# ink_driver.net
KiCad netlist of a schematic drawn in EAGLE
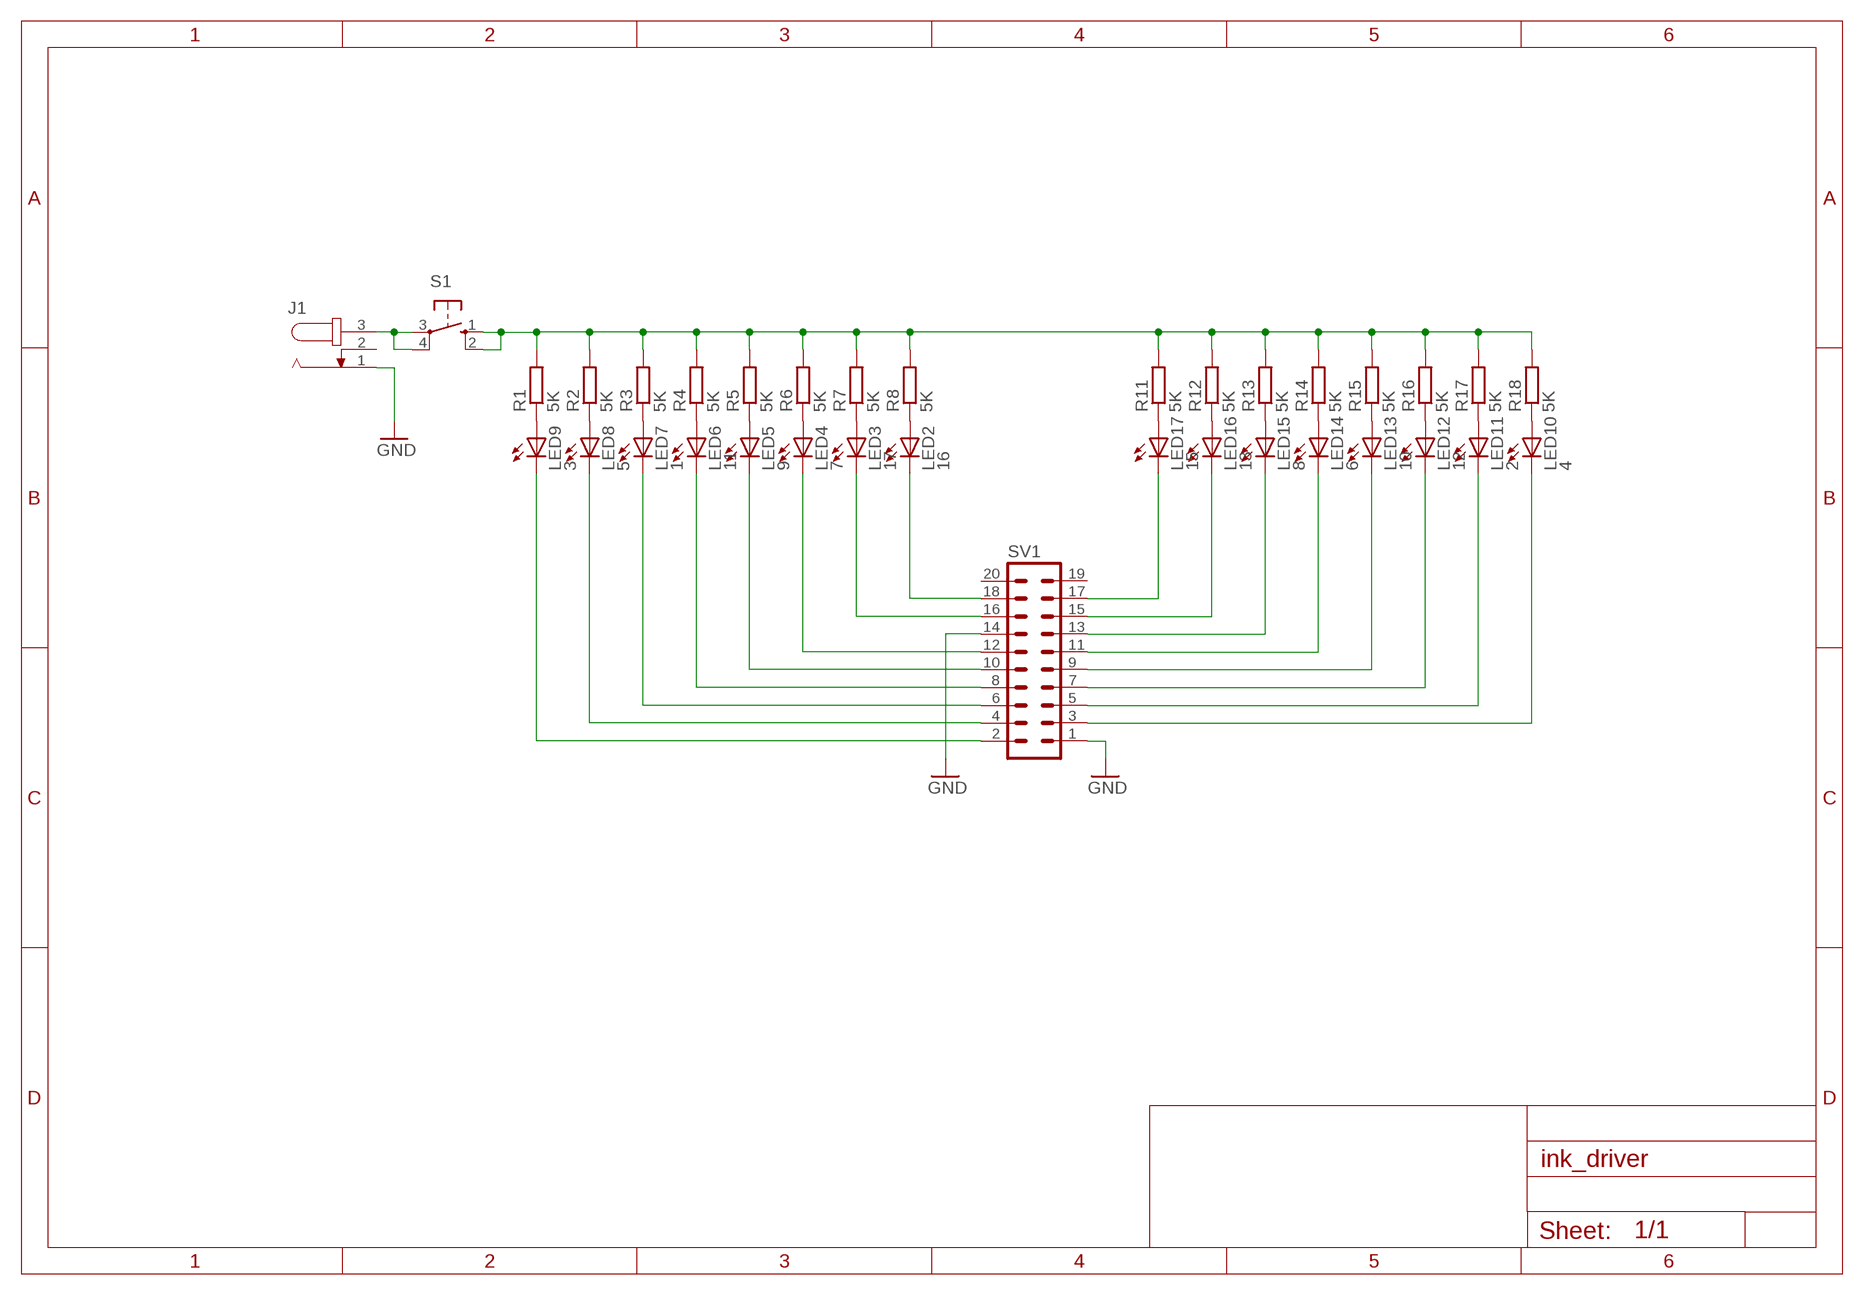
[diagram p0: schematic, sheet 1]

(export (version "E")
  (design (tool "Eeschema 10.0.6"))
  (components
    (comp (ref "J1")
      (value "JACK-PLUG1")
      (footprint "eagle-import:SPC4078")
      (libsource (lib "eagle-import") (part "JACK-PLUG1"))
    )
    (comp (ref "LED2")
      (value "16")
      (footprint "eagle-import:LED3MM")
      (libsource (lib "eagle-import") (part "LED3MM"))
    )
    (comp (ref "LED3")
      (value "17")
      (footprint "eagle-import:LED3MM")
      (libsource (lib "eagle-import") (part "LED3MM"))
    )
    (comp (ref "LED4")
      (value "7")
      (footprint "eagle-import:LED3MM")
      (libsource (lib "eagle-import") (part "LED3MM"))
    )
    (comp (ref "LED5")
      (value "9")
      (footprint "eagle-import:LED3MM")
      (libsource (lib "eagle-import") (part "LED3MM"))
    )
    (comp (ref "LED6")
      (value "11")
      (footprint "eagle-import:LED3MM")
      (libsource (lib "eagle-import") (part "LED3MM"))
    )
    (comp (ref "LED7")
      (value "1")
      (footprint "eagle-import:LED3MM")
      (libsource (lib "eagle-import") (part "LED3MM"))
    )
    (comp (ref "LED8")
      (value "5")
      (footprint "eagle-import:LED3MM")
      (libsource (lib "eagle-import") (part "LED3MM"))
    )
    (comp (ref "LED9")
      (value "3")
      (footprint "eagle-import:LED3MM")
      (libsource (lib "eagle-import") (part "LED3MM"))
    )
    (comp (ref "LED10")
      (value "4")
      (footprint "eagle-import:LED3MM")
      (libsource (lib "eagle-import") (part "LED3MM"))
    )
    (comp (ref "LED11")
      (value "2")
      (footprint "eagle-import:LED3MM")
      (libsource (lib "eagle-import") (part "LED3MM"))
    )
    (comp (ref "LED12")
      (value "12")
      (footprint "eagle-import:LED3MM")
      (libsource (lib "eagle-import") (part "LED3MM"))
    )
    (comp (ref "LED13")
      (value "10")
      (footprint "eagle-import:LED3MM")
      (libsource (lib "eagle-import") (part "LED3MM"))
    )
    (comp (ref "LED14")
      (value "6")
      (footprint "eagle-import:LED3MM")
      (libsource (lib "eagle-import") (part "LED3MM"))
    )
    (comp (ref "LED15")
      (value "8")
      (footprint "eagle-import:LED3MM")
      (libsource (lib "eagle-import") (part "LED3MM"))
    )
    (comp (ref "LED16")
      (value "13")
      (footprint "eagle-import:LED3MM")
      (libsource (lib "eagle-import") (part "LED3MM"))
    )
    (comp (ref "LED17")
      (value "15")
      (footprint "eagle-import:LED3MM")
      (libsource (lib "eagle-import") (part "LED3MM"))
    )
    (comp (ref "R1")
      (value "5K")
      (footprint "eagle-import:0207_10")
      (libsource (lib "eagle-import") (part "R-EU_0207/10"))
    )
    (comp (ref "R2")
      (value "5K")
      (footprint "eagle-import:0207_10")
      (libsource (lib "eagle-import") (part "R-EU_0207/10"))
    )
    (comp (ref "R3")
      (value "5K")
      (footprint "eagle-import:0207_10")
      (libsource (lib "eagle-import") (part "R-EU_0207/10"))
    )
    (comp (ref "R4")
      (value "5K")
      (footprint "eagle-import:0207_10")
      (libsource (lib "eagle-import") (part "R-EU_0207/10"))
    )
    (comp (ref "R5")
      (value "5K")
      (footprint "eagle-import:0207_10")
      (libsource (lib "eagle-import") (part "R-EU_0207/10"))
    )
    (comp (ref "R6")
      (value "5K")
      (footprint "eagle-import:0207_10")
      (libsource (lib "eagle-import") (part "R-EU_0207/10"))
    )
    (comp (ref "R7")
      (value "5K")
      (footprint "eagle-import:0207_10")
      (libsource (lib "eagle-import") (part "R-EU_0207/10"))
    )
    (comp (ref "R8")
      (value "5K")
      (footprint "eagle-import:0207_10")
      (libsource (lib "eagle-import") (part "R-EU_0207/10"))
    )
    (comp (ref "R11")
      (value "5K")
      (footprint "eagle-import:0207_10")
      (libsource (lib "eagle-import") (part "R-EU_0207/10"))
    )
    (comp (ref "R12")
      (value "5K")
      (footprint "eagle-import:0207_10")
      (libsource (lib "eagle-import") (part "R-EU_0207/10"))
    )
    (comp (ref "R13")
      (value "5K")
      (footprint "eagle-import:0207_10")
      (libsource (lib "eagle-import") (part "R-EU_0207/10"))
    )
    (comp (ref "R14")
      (value "5K")
      (footprint "eagle-import:0207_10")
      (libsource (lib "eagle-import") (part "R-EU_0207/10"))
    )
    (comp (ref "R15")
      (value "5K")
      (footprint "eagle-import:0207_10")
      (libsource (lib "eagle-import") (part "R-EU_0207/10"))
    )
    (comp (ref "R16")
      (value "5K")
      (footprint "eagle-import:0207_10")
      (libsource (lib "eagle-import") (part "R-EU_0207/10"))
    )
    (comp (ref "R17")
      (value "5K")
      (footprint "eagle-import:0207_10")
      (libsource (lib "eagle-import") (part "R-EU_0207/10"))
    )
    (comp (ref "R18")
      (value "5K")
      (footprint "eagle-import:0207_10")
      (libsource (lib "eagle-import") (part "R-EU_0207/10"))
    )
    (comp (ref "S1")
      (value "10-XX")
      (footprint "eagle-import:B3F-10XX")
      (libsource (lib "eagle-import") (part "10-XX"))
    )
    (comp (ref "SV1")
      (value "ML20")
      (footprint "eagle-import:ML20")
      (libsource (lib "eagle-import") (part "ML20"))
    )
  )
  (nets
    (net (code "1") (name "GND") (class "Default")
      (node (ref "J1") (pin "1") (pinfunction "1_1") (pintype "passive"))
      (node (ref "SV1") (pin "1") (pinfunction "1_1") (pintype "passive"))
      (node (ref "SV1") (pin "14") (pinfunction "14_14") (pintype "passive"))
    )
    (net (code "2") (name "Net-(LED2-C)") (class "Default")
      (node (ref "LED2") (pin "K") (pinfunction "C_K") (pintype "passive"))
      (node (ref "SV1") (pin "18") (pinfunction "18_18") (pintype "passive"))
    )
    (net (code "3") (name "Net-(LED2-PadA)") (class "Default")
      (node (ref "LED2") (pin "A") (pinfunction "A_A") (pintype "passive"))
      (node (ref "R8") (pin "1") (pinfunction "1_1") (pintype "passive"))
    )
    (net (code "4") (name "Net-(LED3-C)") (class "Default")
      (node (ref "LED3") (pin "K") (pinfunction "C_K") (pintype "passive"))
      (node (ref "SV1") (pin "16") (pinfunction "16_16") (pintype "passive"))
    )
    (net (code "5") (name "Net-(LED3-PadA)") (class "Default")
      (node (ref "LED3") (pin "A") (pinfunction "A_A") (pintype "passive"))
      (node (ref "R7") (pin "1") (pinfunction "1_1") (pintype "passive"))
    )
    (net (code "6") (name "Net-(LED4-C)") (class "Default")
      (node (ref "LED4") (pin "K") (pinfunction "C_K") (pintype "passive"))
      (node (ref "SV1") (pin "12") (pinfunction "12_12") (pintype "passive"))
    )
    (net (code "7") (name "Net-(LED4-PadA)") (class "Default")
      (node (ref "LED4") (pin "A") (pinfunction "A_A") (pintype "passive"))
      (node (ref "R6") (pin "1") (pinfunction "1_1") (pintype "passive"))
    )
    (net (code "8") (name "Net-(LED5-C)") (class "Default")
      (node (ref "LED5") (pin "K") (pinfunction "C_K") (pintype "passive"))
      (node (ref "SV1") (pin "10") (pinfunction "10_10") (pintype "passive"))
    )
    (net (code "9") (name "Net-(LED5-PadA)") (class "Default")
      (node (ref "LED5") (pin "A") (pinfunction "A_A") (pintype "passive"))
      (node (ref "R5") (pin "1") (pinfunction "1_1") (pintype "passive"))
    )
    (net (code "10") (name "Net-(LED6-C)") (class "Default")
      (node (ref "LED6") (pin "K") (pinfunction "C_K") (pintype "passive"))
      (node (ref "SV1") (pin "8") (pinfunction "8_8") (pintype "passive"))
    )
    (net (code "11") (name "Net-(LED6-PadA)") (class "Default")
      (node (ref "LED6") (pin "A") (pinfunction "A_A") (pintype "passive"))
      (node (ref "R4") (pin "1") (pinfunction "1_1") (pintype "passive"))
    )
    (net (code "12") (name "Net-(LED7-C)") (class "Default")
      (node (ref "LED7") (pin "K") (pinfunction "C_K") (pintype "passive"))
      (node (ref "SV1") (pin "6") (pinfunction "6_6") (pintype "passive"))
    )
    (net (code "13") (name "Net-(LED7-PadA)") (class "Default")
      (node (ref "LED7") (pin "A") (pinfunction "A_A") (pintype "passive"))
      (node (ref "R3") (pin "1") (pinfunction "1_1") (pintype "passive"))
    )
    (net (code "14") (name "Net-(LED8-C)") (class "Default")
      (node (ref "LED8") (pin "K") (pinfunction "C_K") (pintype "passive"))
      (node (ref "SV1") (pin "4") (pinfunction "4_4") (pintype "passive"))
    )
    (net (code "15") (name "Net-(LED8-PadA)") (class "Default")
      (node (ref "LED8") (pin "A") (pinfunction "A_A") (pintype "passive"))
      (node (ref "R2") (pin "1") (pinfunction "1_1") (pintype "passive"))
    )
    (net (code "16") (name "Net-(LED9-C)") (class "Default")
      (node (ref "LED9") (pin "K") (pinfunction "C_K") (pintype "passive"))
      (node (ref "SV1") (pin "2") (pinfunction "2_2") (pintype "passive"))
    )
    (net (code "17") (name "Net-(LED9-PadA)") (class "Default")
      (node (ref "LED9") (pin "A") (pinfunction "A_A") (pintype "passive"))
      (node (ref "R1") (pin "1") (pinfunction "1_1") (pintype "passive"))
    )
    (net (code "18") (name "Net-(LED10-C)") (class "Default")
      (node (ref "LED10") (pin "K") (pinfunction "C_K") (pintype "passive"))
      (node (ref "SV1") (pin "3") (pinfunction "3_3") (pintype "passive"))
    )
    (net (code "19") (name "Net-(LED10-PadA)") (class "Default")
      (node (ref "LED10") (pin "A") (pinfunction "A_A") (pintype "passive"))
      (node (ref "R18") (pin "1") (pinfunction "1_1") (pintype "passive"))
    )
    (net (code "20") (name "Net-(LED11-C)") (class "Default")
      (node (ref "LED11") (pin "K") (pinfunction "C_K") (pintype "passive"))
      (node (ref "SV1") (pin "5") (pinfunction "5_5") (pintype "passive"))
    )
    (net (code "21") (name "Net-(LED11-PadA)") (class "Default")
      (node (ref "LED11") (pin "A") (pinfunction "A_A") (pintype "passive"))
      (node (ref "R17") (pin "1") (pinfunction "1_1") (pintype "passive"))
    )
    (net (code "22") (name "Net-(LED12-C)") (class "Default")
      (node (ref "LED12") (pin "K") (pinfunction "C_K") (pintype "passive"))
      (node (ref "SV1") (pin "7") (pinfunction "7_7") (pintype "passive"))
    )
    (net (code "23") (name "Net-(LED12-PadA)") (class "Default")
      (node (ref "LED12") (pin "A") (pinfunction "A_A") (pintype "passive"))
      (node (ref "R16") (pin "1") (pinfunction "1_1") (pintype "passive"))
    )
    (net (code "24") (name "Net-(LED13-C)") (class "Default")
      (node (ref "LED13") (pin "K") (pinfunction "C_K") (pintype "passive"))
      (node (ref "SV1") (pin "9") (pinfunction "9_9") (pintype "passive"))
    )
    (net (code "25") (name "Net-(LED13-PadA)") (class "Default")
      (node (ref "LED13") (pin "A") (pinfunction "A_A") (pintype "passive"))
      (node (ref "R15") (pin "1") (pinfunction "1_1") (pintype "passive"))
    )
    (net (code "26") (name "Net-(LED14-C)") (class "Default")
      (node (ref "LED14") (pin "K") (pinfunction "C_K") (pintype "passive"))
      (node (ref "SV1") (pin "11") (pinfunction "11_11") (pintype "passive"))
    )
    (net (code "27") (name "Net-(LED14-PadA)") (class "Default")
      (node (ref "LED14") (pin "A") (pinfunction "A_A") (pintype "passive"))
      (node (ref "R14") (pin "1") (pinfunction "1_1") (pintype "passive"))
    )
    (net (code "28") (name "Net-(LED15-C)") (class "Default")
      (node (ref "LED15") (pin "K") (pinfunction "C_K") (pintype "passive"))
      (node (ref "SV1") (pin "13") (pinfunction "13_13") (pintype "passive"))
    )
    (net (code "29") (name "Net-(LED15-PadA)") (class "Default")
      (node (ref "LED15") (pin "A") (pinfunction "A_A") (pintype "passive"))
      (node (ref "R13") (pin "1") (pinfunction "1_1") (pintype "passive"))
    )
    (net (code "30") (name "Net-(LED16-C)") (class "Default")
      (node (ref "LED16") (pin "K") (pinfunction "C_K") (pintype "passive"))
      (node (ref "SV1") (pin "15") (pinfunction "15_15") (pintype "passive"))
    )
    (net (code "31") (name "Net-(LED16-PadA)") (class "Default")
      (node (ref "LED16") (pin "A") (pinfunction "A_A") (pintype "passive"))
      (node (ref "R12") (pin "1") (pinfunction "1_1") (pintype "passive"))
    )
    (net (code "32") (name "Net-(LED17-C)") (class "Default")
      (node (ref "LED17") (pin "K") (pinfunction "C_K") (pintype "passive"))
      (node (ref "SV1") (pin "17") (pinfunction "17_17") (pintype "passive"))
    )
    (net (code "33") (name "Net-(LED17-PadA)") (class "Default")
      (node (ref "LED17") (pin "A") (pinfunction "A_A") (pintype "passive"))
      (node (ref "R11") (pin "1") (pinfunction "1_1") (pintype "passive"))
    )
    (net (code "34") (name "Net-(S1-P)") (class "Default")
      (node (ref "J1") (pin "3") (pinfunction "3_3") (pintype "passive"))
      (node (ref "S1") (pin "3") (pinfunction "P_3") (pintype "passive"))
      (node (ref "S1") (pin "4") (pinfunction "P1_4") (pintype "passive"))
    )
    (net (code "35") (name "Net-(S1-S)") (class "Default")
      (node (ref "R1") (pin "2") (pinfunction "2_2") (pintype "passive"))
      (node (ref "R11") (pin "2") (pinfunction "2_2") (pintype "passive"))
      (node (ref "R12") (pin "2") (pinfunction "2_2") (pintype "passive"))
      (node (ref "R13") (pin "2") (pinfunction "2_2") (pintype "passive"))
      (node (ref "R14") (pin "2") (pinfunction "2_2") (pintype "passive"))
      (node (ref "R15") (pin "2") (pinfunction "2_2") (pintype "passive"))
      (node (ref "R16") (pin "2") (pinfunction "2_2") (pintype "passive"))
      (node (ref "R17") (pin "2") (pinfunction "2_2") (pintype "passive"))
      (node (ref "R18") (pin "2") (pinfunction "2_2") (pintype "passive"))
      (node (ref "R2") (pin "2") (pinfunction "2_2") (pintype "passive"))
      (node (ref "R3") (pin "2") (pinfunction "2_2") (pintype "passive"))
      (node (ref "R4") (pin "2") (pinfunction "2_2") (pintype "passive"))
      (node (ref "R5") (pin "2") (pinfunction "2_2") (pintype "passive"))
      (node (ref "R6") (pin "2") (pinfunction "2_2") (pintype "passive"))
      (node (ref "R7") (pin "2") (pinfunction "2_2") (pintype "passive"))
      (node (ref "R8") (pin "2") (pinfunction "2_2") (pintype "passive"))
      (node (ref "S1") (pin "1") (pinfunction "S_1") (pintype "passive"))
      (node (ref "S1") (pin "2") (pinfunction "S1_2") (pintype "passive"))
    )
    (net (code "36") (name "unconnected-(J1-Pad2)") (class "Default")
      (node (ref "J1") (pin "2") (pinfunction "2_2") (pintype "passive"))
    )
    (net (code "37") (name "unconnected-(SV1-Pad19)") (class "Default")
      (node (ref "SV1") (pin "19") (pinfunction "19_19") (pintype "passive"))
    )
    (net (code "38") (name "unconnected-(SV1-Pad20)") (class "Default")
      (node (ref "SV1") (pin "20") (pinfunction "20_20") (pintype "passive"))
    )
  )
)
